# MainSheet.net
KiCad netlist of a schematic drawn in Altium Designer
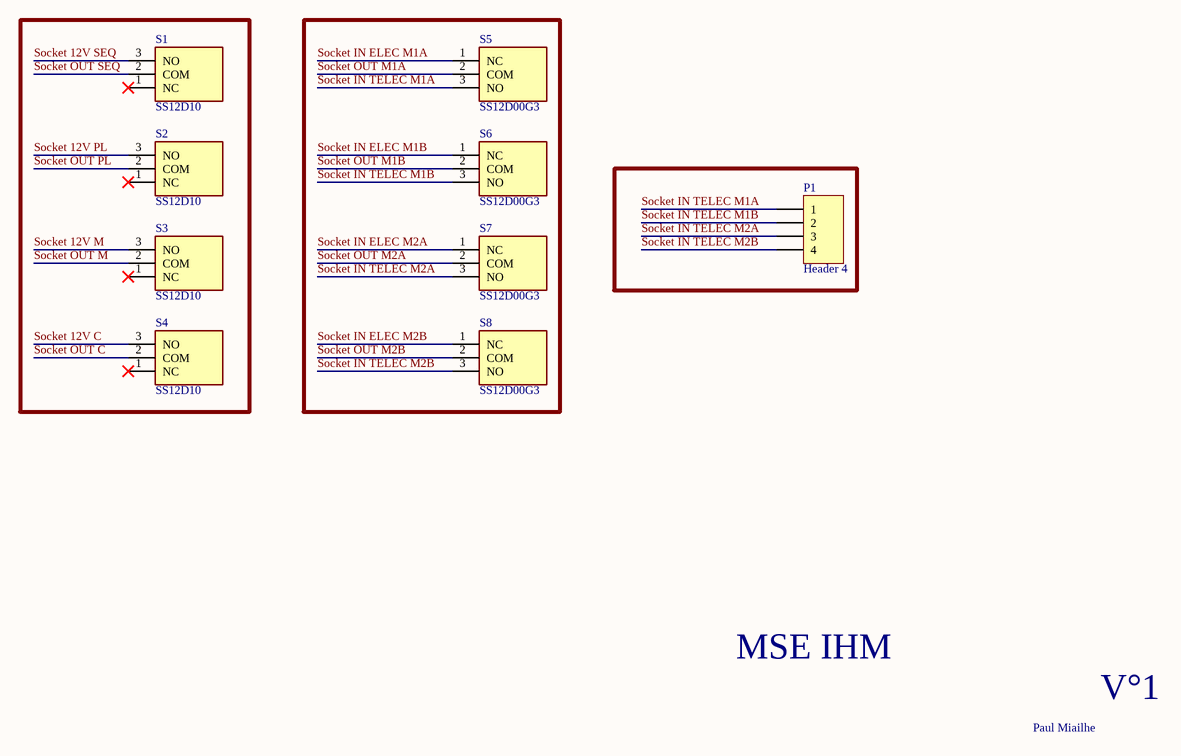
[diagram p0: MainSheet.SchDoc]

(export (version "E")
  (design (tool "Eeschema 10.0.6"))
  (components
    (comp (ref "P1")
      (value "Header 4")
      (footprint "HDR1X4")
      (description "Header, 4-Pin")
      (fields (field (name "PUBLISHER") "Altium Limited"))
      (libsource (lib "Miscellaneous Connectors") (part "Header 4"))
    )
    (comp (ref "S1")
      (value "SS12D10")
      (footprint "SamacSys:SS12D10")
      (description "Switch")
      (libsource (lib "*") (part "SS12D10"))
    )
    (comp (ref "S2")
      (value "SS12D10")
      (footprint "SamacSys:SS12D10")
      (description "Switch")
      (libsource (lib "*") (part "SS12D10"))
    )
    (comp (ref "S3")
      (value "SS12D10")
      (footprint "SamacSys:SS12D10")
      (description "Switch")
      (libsource (lib "*") (part "SS12D10"))
    )
    (comp (ref "S4")
      (value "SS12D10")
      (footprint "SamacSys:SS12D10")
      (description "Switch")
      (libsource (lib "*") (part "SS12D10"))
    )
    (comp (ref "S5")
      (value "SS12D00G3")
      (footprint "SamacSys:SS12D00G3")
      (description "Switch")
      (libsource (lib "*") (part "SS12D00G3"))
    )
    (comp (ref "S6")
      (value "SS12D00G3")
      (footprint "SamacSys:SS12D00G3")
      (description "Switch")
      (libsource (lib "*") (part "SS12D00G3"))
    )
    (comp (ref "S7")
      (value "SS12D00G3")
      (footprint "SamacSys:SS12D00G3")
      (description "Switch")
      (libsource (lib "*") (part "SS12D00G3"))
    )
    (comp (ref "S8")
      (value "SS12D00G3")
      (footprint "SamacSys:SS12D00G3")
      (description "Switch")
      (libsource (lib "*") (part "SS12D00G3"))
    )
  )
  (nets
    (net (code "1") (name "/Socket 12V C") (class "Default")
      (node (ref "S4") (pin "3") (pinfunction "NO_3") (pintype "passive"))
    )
    (net (code "2") (name "/Socket 12V M") (class "Default")
      (node (ref "S3") (pin "3") (pinfunction "NO_3") (pintype "passive"))
    )
    (net (code "3") (name "/Socket 12V PL") (class "Default")
      (node (ref "S2") (pin "3") (pinfunction "NO_3") (pintype "passive"))
    )
    (net (code "4") (name "/Socket 12V SEQ") (class "Default")
      (node (ref "S1") (pin "3") (pinfunction "NO_3") (pintype "passive"))
    )
    (net (code "5") (name "/Socket IN ELEC M1A") (class "Default")
      (node (ref "S5") (pin "1") (pinfunction "NC_1") (pintype "passive"))
    )
    (net (code "6") (name "/Socket IN ELEC M1B") (class "Default")
      (node (ref "S6") (pin "1") (pinfunction "NC_1") (pintype "passive"))
    )
    (net (code "7") (name "/Socket IN ELEC M2A") (class "Default")
      (node (ref "S7") (pin "1") (pinfunction "NC_1") (pintype "passive"))
    )
    (net (code "8") (name "/Socket IN ELEC M2B") (class "Default")
      (node (ref "S8") (pin "1") (pinfunction "NC_1") (pintype "passive"))
    )
    (net (code "9") (name "/Socket IN TELEC M1A") (class "Default")
      (node (ref "P1") (pin "1") (pinfunction "1_1") (pintype "passive"))
      (node (ref "S5") (pin "3") (pinfunction "NO_3") (pintype "passive"))
    )
    (net (code "10") (name "/Socket IN TELEC M1B") (class "Default")
      (node (ref "P1") (pin "2") (pinfunction "2_2") (pintype "passive"))
      (node (ref "S6") (pin "3") (pinfunction "NO_3") (pintype "passive"))
    )
    (net (code "11") (name "/Socket IN TELEC M2A") (class "Default")
      (node (ref "P1") (pin "3") (pinfunction "3_3") (pintype "passive"))
      (node (ref "S7") (pin "3") (pinfunction "NO_3") (pintype "passive"))
    )
    (net (code "12") (name "/Socket IN TELEC M2B") (class "Default")
      (node (ref "P1") (pin "4") (pinfunction "4_4") (pintype "passive"))
      (node (ref "S8") (pin "3") (pinfunction "NO_3") (pintype "passive"))
    )
    (net (code "13") (name "/Socket OUT C") (class "Default")
      (node (ref "S4") (pin "2") (pinfunction "COM_2") (pintype "passive"))
    )
    (net (code "14") (name "/Socket OUT M") (class "Default")
      (node (ref "S3") (pin "2") (pinfunction "COM_2") (pintype "passive"))
    )
    (net (code "15") (name "/Socket OUT M1A") (class "Default")
      (node (ref "S5") (pin "2") (pinfunction "COM_2") (pintype "passive"))
    )
    (net (code "16") (name "/Socket OUT M1B") (class "Default")
      (node (ref "S6") (pin "2") (pinfunction "COM_2") (pintype "passive"))
    )
    (net (code "17") (name "/Socket OUT M2A") (class "Default")
      (node (ref "S7") (pin "2") (pinfunction "COM_2") (pintype "passive"))
    )
    (net (code "18") (name "/Socket OUT M2B") (class "Default")
      (node (ref "S8") (pin "2") (pinfunction "COM_2") (pintype "passive"))
    )
    (net (code "19") (name "/Socket OUT PL") (class "Default")
      (node (ref "S2") (pin "2") (pinfunction "COM_2") (pintype "passive"))
    )
    (net (code "20") (name "/Socket OUT SEQ") (class "Default")
      (node (ref "S1") (pin "2") (pinfunction "COM_2") (pintype "passive"))
    )
    (net (code "21") (name "unconnected-(S1-NC-Pad1)") (class "Default")
      (node (ref "S1") (pin "1") (pinfunction "NC_1") (pintype "passive+no_connect"))
    )
    (net (code "22") (name "unconnected-(S2-NC-Pad1)") (class "Default")
      (node (ref "S2") (pin "1") (pinfunction "NC_1") (pintype "passive+no_connect"))
    )
    (net (code "23") (name "unconnected-(S3-NC-Pad1)") (class "Default")
      (node (ref "S3") (pin "1") (pinfunction "NC_1") (pintype "passive+no_connect"))
    )
    (net (code "24") (name "unconnected-(S4-NC-Pad1)") (class "Default")
      (node (ref "S4") (pin "1") (pinfunction "NC_1") (pintype "passive+no_connect"))
    )
  )
)
